# kit.net
KiCad netlist of a schematic drawn in EAGLE
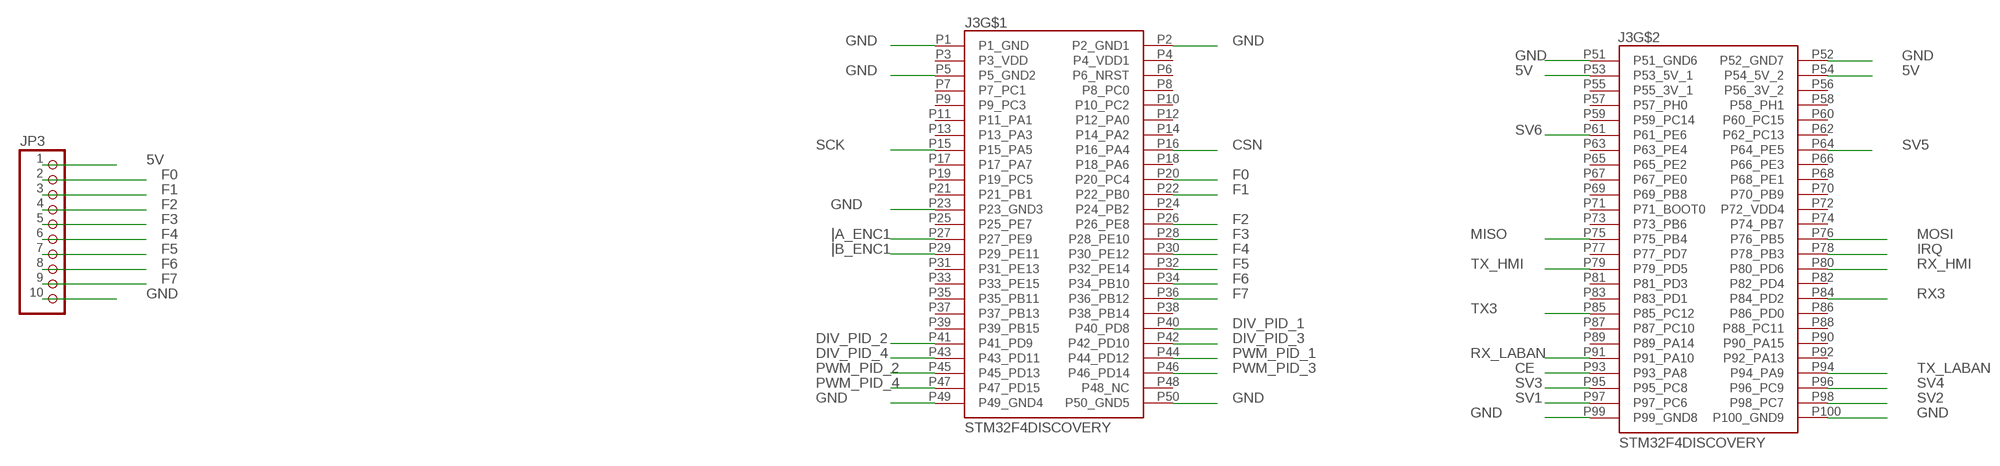
[diagram p0: schematic, sheet 1]
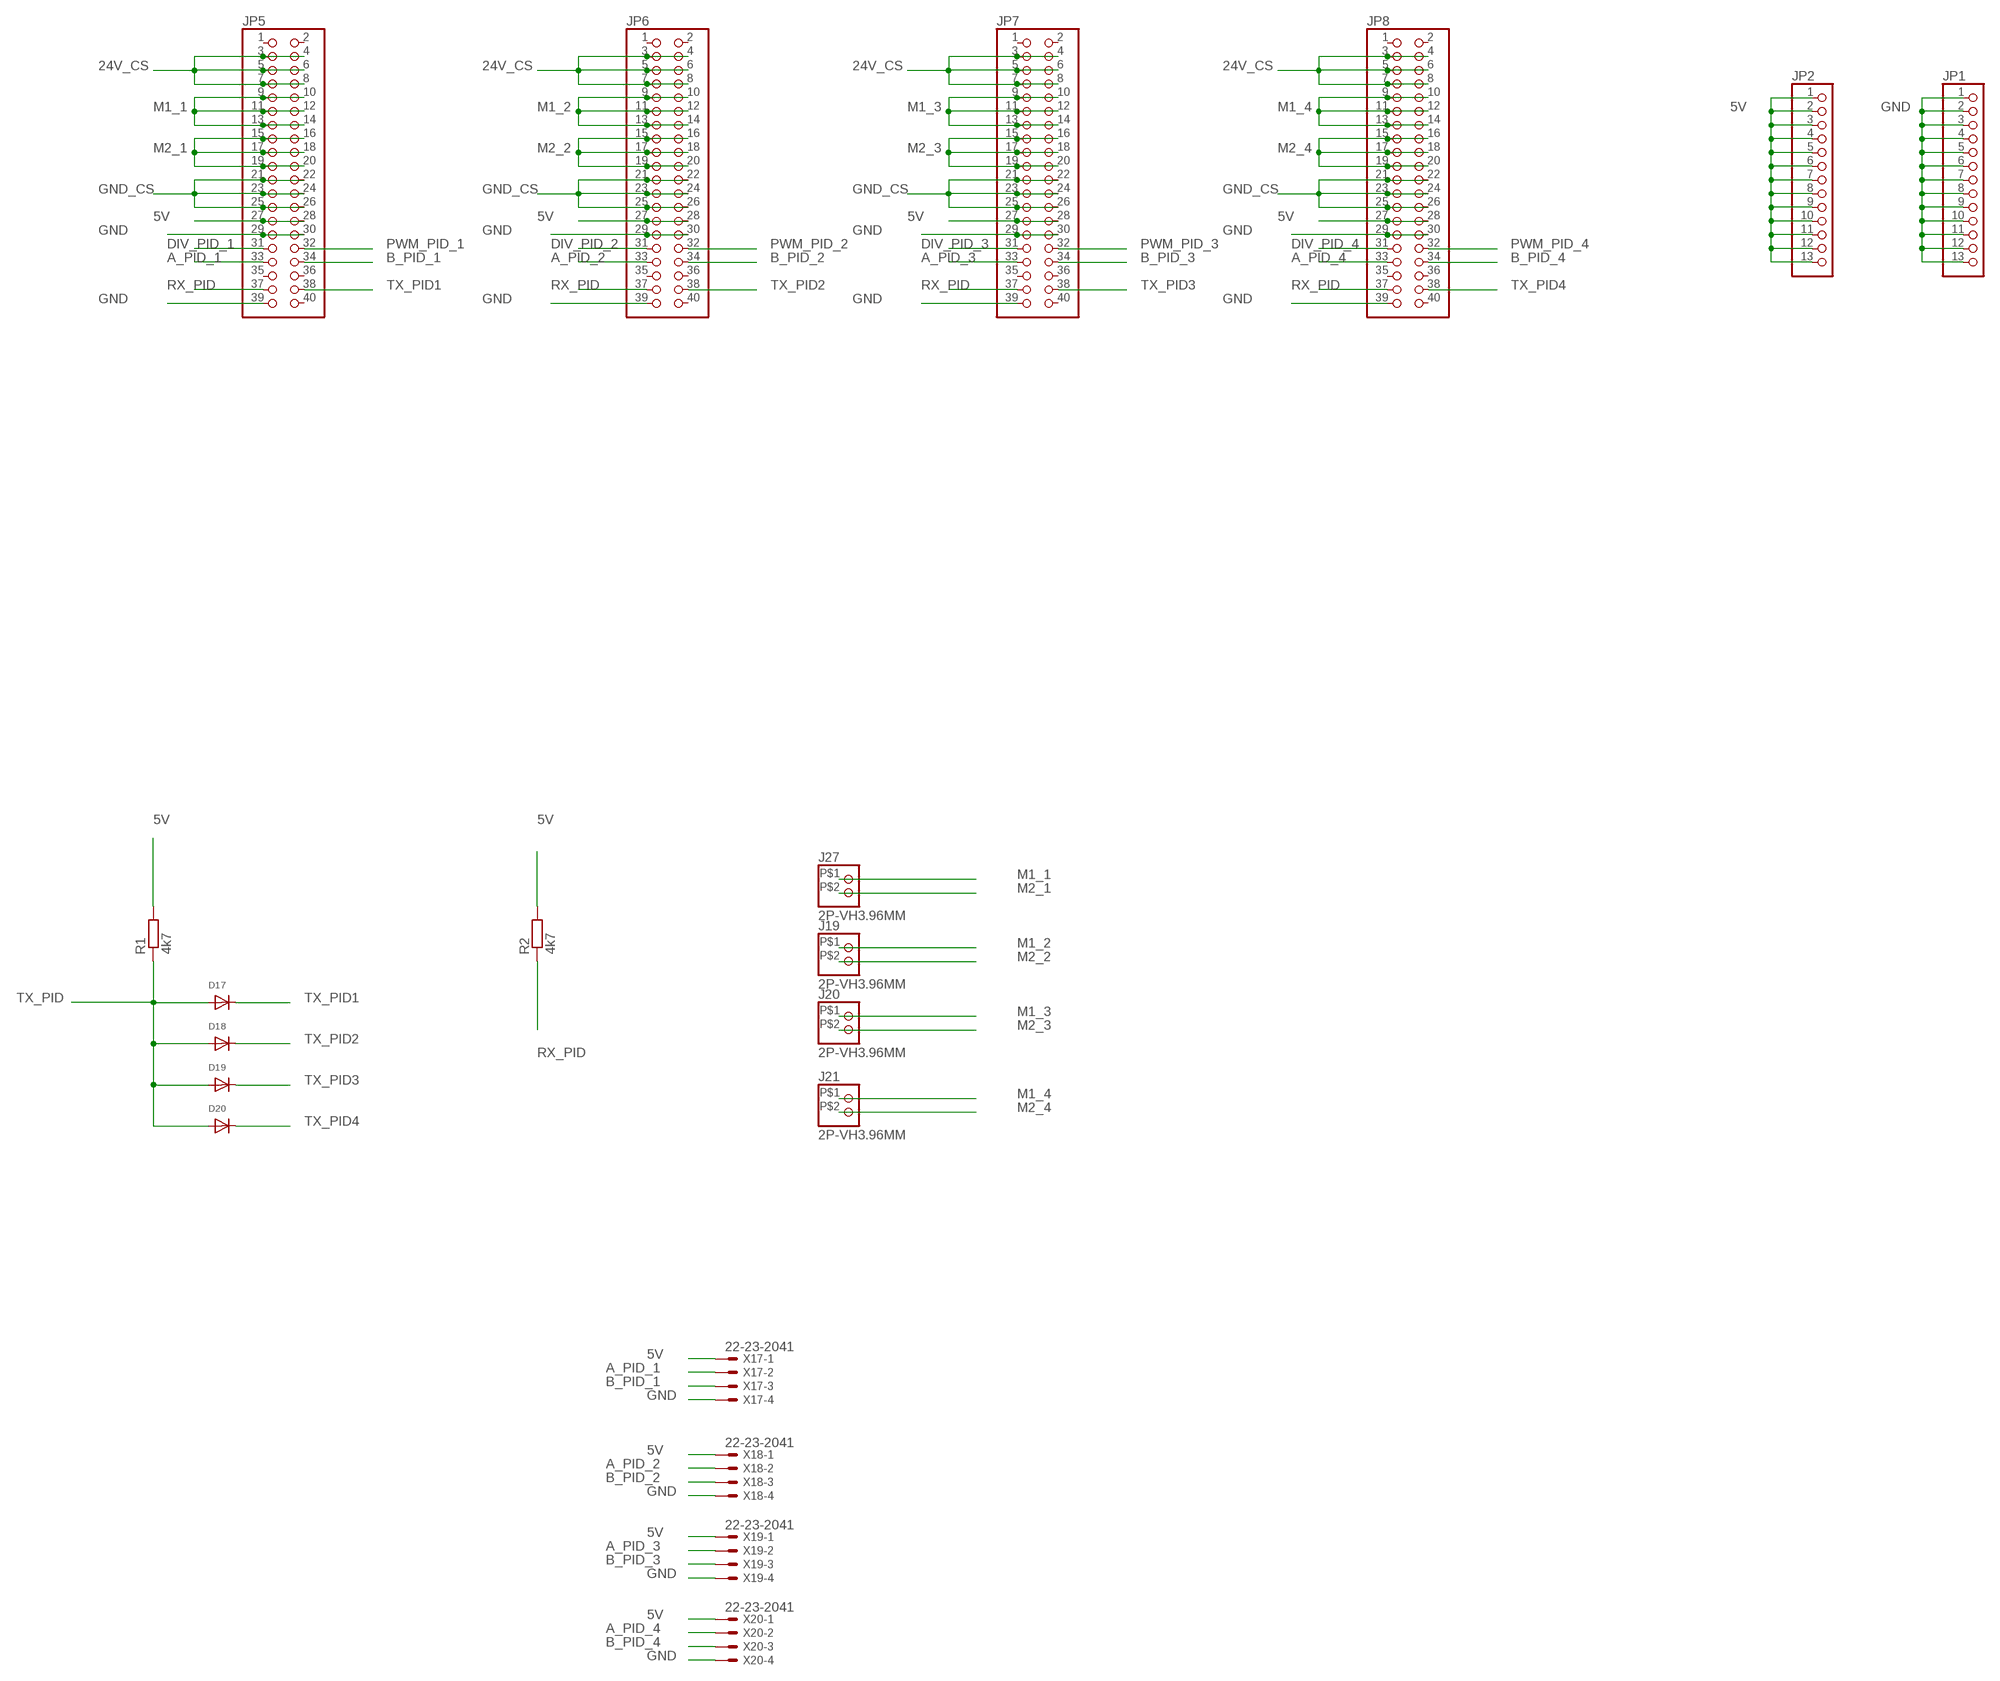
[diagram p1: schematic, sheet 2]
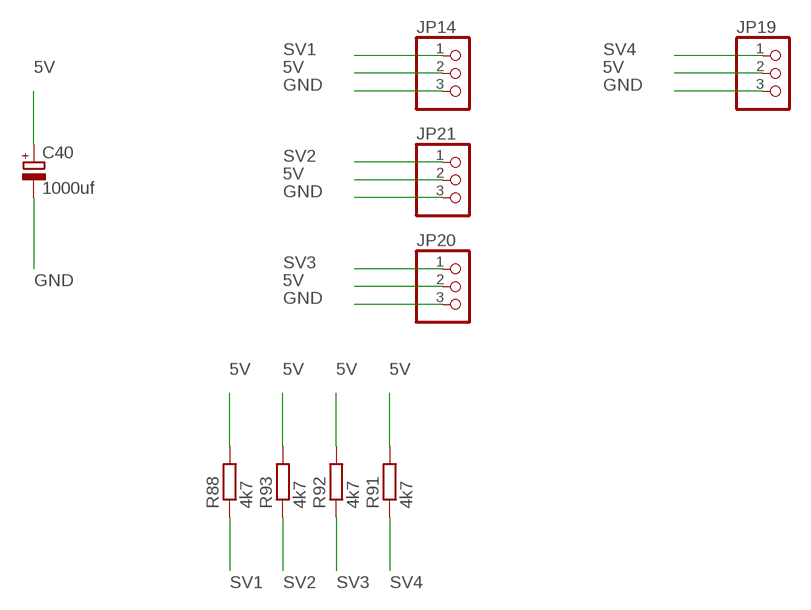
[diagram p2: schematic, sheet 3]
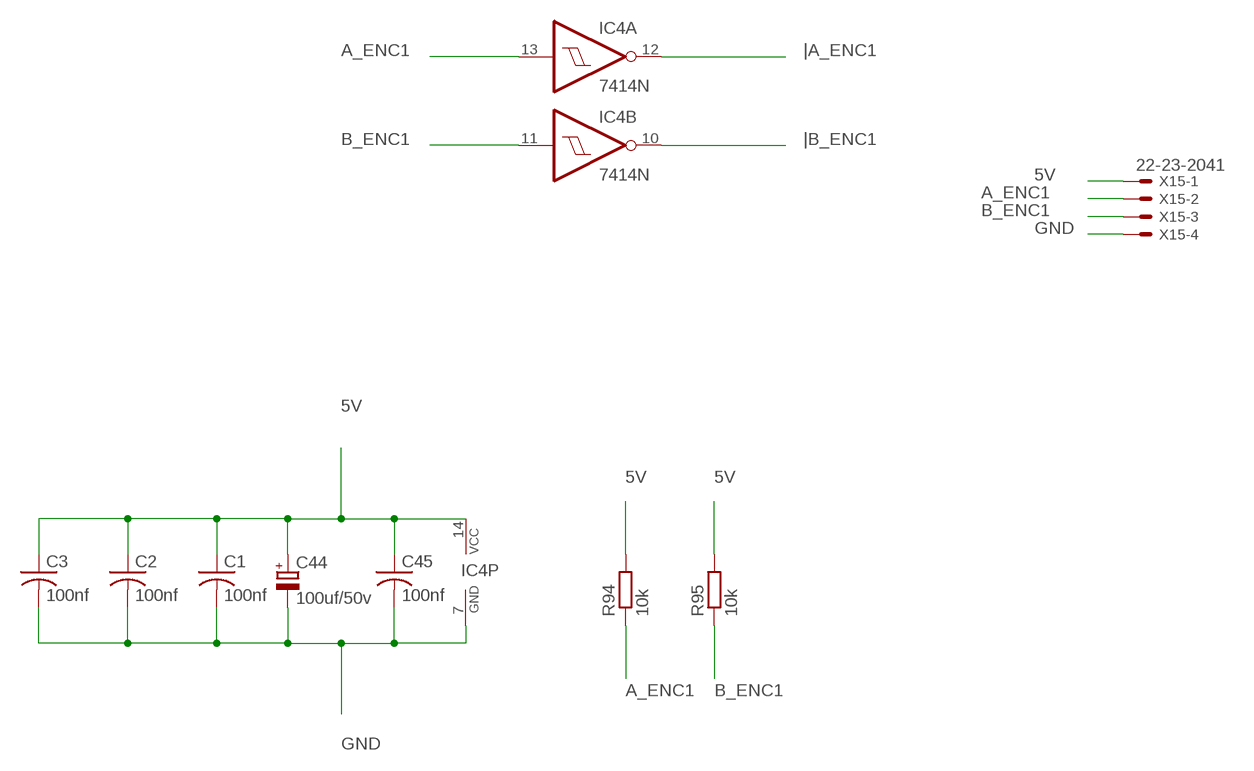
[diagram p3: schematic, sheet 4]
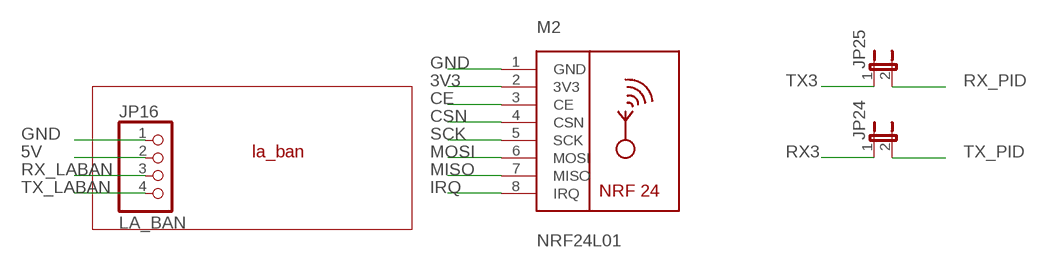
[diagram p4: schematic, sheet 5]
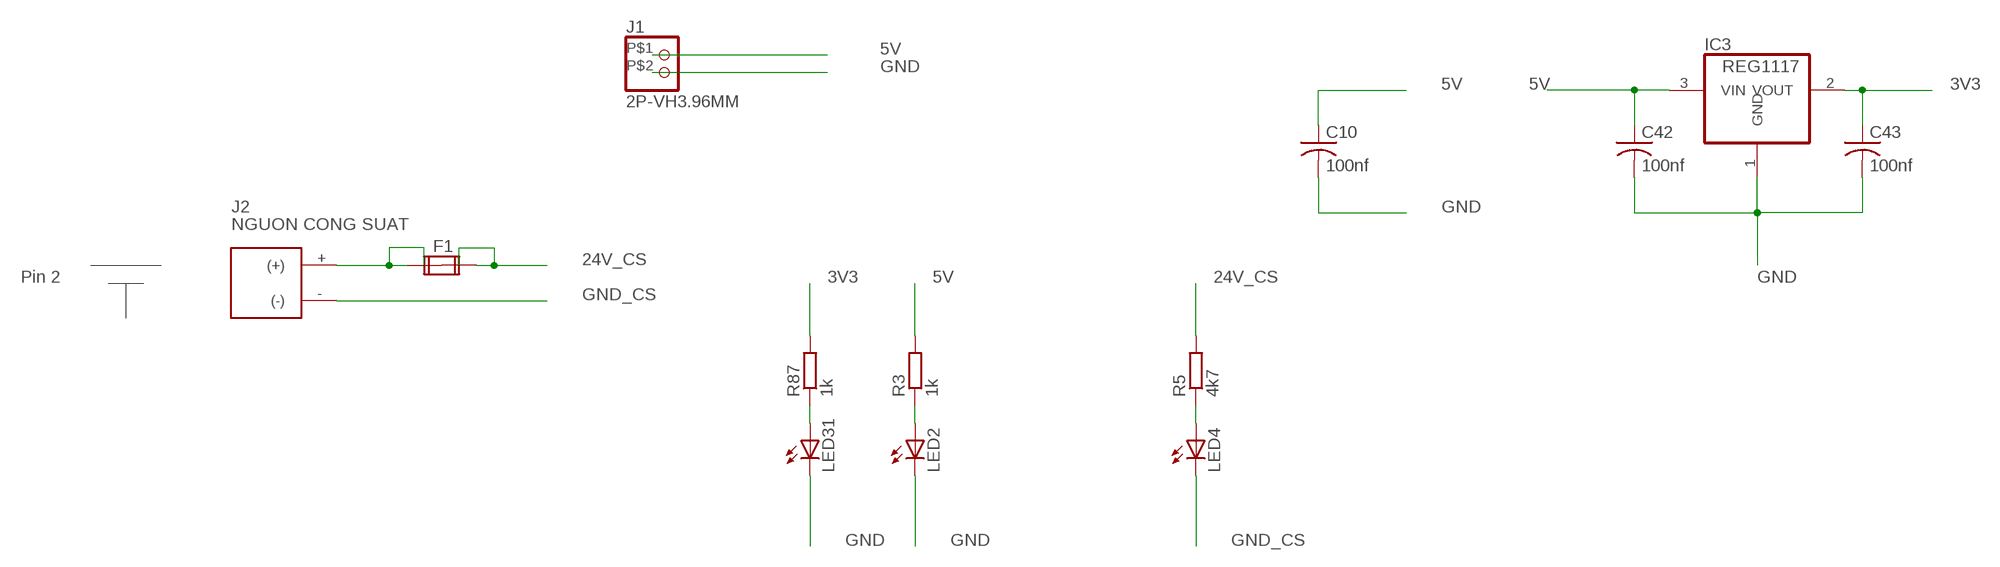
[diagram p5: schematic, sheet 6]

(export (version "E")
  (design (tool "Eeschema 10.0.6"))
  (components
    (comp (ref "C1")
      (value "100nf")
      (footprint "eagle-import:C050-025X075")
      (libsource (lib "eagle-import") (part "C-US050-025X075"))
    )
    (comp (ref "C2")
      (value "100nf")
      (footprint "eagle-import:C050-025X075")
      (libsource (lib "eagle-import") (part "C-US050-025X075"))
    )
    (comp (ref "C3")
      (value "100nf")
      (footprint "eagle-import:C050-025X075")
      (libsource (lib "eagle-import") (part "C-US050-025X075"))
    )
    (comp (ref "C44")
      (value "100uf/50v")
      (footprint "eagle-import:E5-10,5")
      (libsource (lib "eagle-import") (part "CPOL-EUE5-10.5"))
    )
    (comp (ref "C45")
      (value "100nf")
      (footprint "eagle-import:C050-025X075")
      (libsource (lib "eagle-import") (part "C-US050-025X075"))
    )
    (comp (ref "IC4")
      (value "7414N")
      (footprint "eagle-import:DIL14")
      (libsource (lib "eagle-import") (part "7414N"))
    )
    (comp (ref "R94")
      (value "10k")
      (footprint "eagle-import:0207_10")
      (libsource (lib "eagle-import") (part "R-EU_0207/10"))
    )
    (comp (ref "R95")
      (value "10k")
      (footprint "eagle-import:0207_10")
      (libsource (lib "eagle-import") (part "R-EU_0207/10"))
    )
    (comp (ref "X15")
      (value "22-23-2041")
      (footprint "eagle-import:22-23-2041")
      (fields (field (name "MF") "MOLEX"))
      (libsource (lib "eagle-import") (part "22-23-2041"))
    )
    (comp (ref "C40")
      (value "1000uf")
      (footprint "eagle-import:E5-10,5")
      (libsource (lib "eagle-import") (part "CPOL-EUE5-10.5"))
    )
    (comp (ref "JP14")
      (value "PINHD-1X3")
      (footprint "eagle-import:1X03")
      (libsource (lib "eagle-import") (part "PINHD-1X3"))
    )
    (comp (ref "JP19")
      (value "PINHD-1X3")
      (footprint "eagle-import:1X03")
      (libsource (lib "eagle-import") (part "PINHD-1X3"))
    )
    (comp (ref "JP20")
      (value "PINHD-1X3")
      (footprint "eagle-import:1X03")
      (libsource (lib "eagle-import") (part "PINHD-1X3"))
    )
    (comp (ref "JP21")
      (value "PINHD-1X3")
      (footprint "eagle-import:1X03")
      (libsource (lib "eagle-import") (part "PINHD-1X3"))
    )
    (comp (ref "R88")
      (value "4k7")
      (footprint "eagle-import:0207_10")
      (libsource (lib "eagle-import") (part "R-EU_0207/10"))
    )
    (comp (ref "R91")
      (value "4k7")
      (footprint "eagle-import:0207_10")
      (libsource (lib "eagle-import") (part "R-EU_0207/10"))
    )
    (comp (ref "R92")
      (value "4k7")
      (footprint "eagle-import:0207_10")
      (libsource (lib "eagle-import") (part "R-EU_0207/10"))
    )
    (comp (ref "R93")
      (value "4k7")
      (footprint "eagle-import:0207_10")
      (libsource (lib "eagle-import") (part "R-EU_0207/10"))
    )
    (comp (ref "J3")
      (value "STM32F4DISCOVERY")
      (footprint "eagle-import:STMICROELECTRONICS_STM32F4DISCOVERY")
      (fields (field (name "MF") "STMicroelectronics"))
      (libsource (lib "eagle-import") (part "STM32F4DISCOVERY"))
    )
    (comp (ref "JP3")
      (value "PINHD-1X10/90")
      (footprint "eagle-import:1X10_90")
      (libsource (lib "eagle-import") (part "PINHD-1X10/90"))
    )
    (comp (ref "C10")
      (value "100nf")
      (footprint "eagle-import:C050-025X075")
      (libsource (lib "eagle-import") (part "C-US050-025X075"))
    )
    (comp (ref "C42")
      (value "100nf")
      (footprint "eagle-import:C050-025X075")
      (libsource (lib "eagle-import") (part "C-US050-025X075"))
    )
    (comp (ref "C43")
      (value "100nf")
      (footprint "eagle-import:C050-025X075")
      (libsource (lib "eagle-import") (part "C-US050-025X075"))
    )
    (comp (ref "F1")
      (value "FUSE2P")
      (footprint "eagle-import:FUSE1")
      (libsource (lib "eagle-import") (part "FUSE2P"))
    )
    (comp (ref "IC3")
      (value "REG1117")
      (footprint "eagle-import:SOT223")
      (libsource (lib "eagle-import") (part "REG1117"))
    )
    (comp (ref "J1")
      (value "2P-VH3.96MM")
      (footprint "eagle-import:2P-VH3.96MM")
      (libsource (lib "eagle-import") (part "2P-VH3.96MM"))
    )
    (comp (ref "J2")
      (value "NGUON CONG SUAT")
      (footprint "eagle-import:XT-60")
      (libsource (lib "eagle-import") (part "JACK-DC"))
    )
    (comp (ref "LED2")
      (value "LED3MM")
      (footprint "eagle-import:LED3MM")
      (libsource (lib "eagle-import") (part "LED3MM"))
    )
    (comp (ref "LED4")
      (value "LED3MM")
      (footprint "eagle-import:LED3MM")
      (libsource (lib "eagle-import") (part "LED3MM"))
    )
    (comp (ref "LED31")
      (value "LED3MM")
      (footprint "eagle-import:LED3MM")
      (libsource (lib "eagle-import") (part "LED3MM"))
    )
    (comp (ref "R3")
      (value "1k")
      (footprint "eagle-import:0207_10")
      (libsource (lib "eagle-import") (part "R-EU_0207/10"))
    )
    (comp (ref "R5")
      (value "4k7")
      (footprint "eagle-import:0207_10")
      (libsource (lib "eagle-import") (part "R-EU_0207/10"))
    )
    (comp (ref "R87")
      (value "1k")
      (footprint "eagle-import:0207_10")
      (libsource (lib "eagle-import") (part "R-EU_0207/10"))
    )
    (comp (ref "D17")
      (value "DIODEDO-1N4148")
      (footprint "eagle-import:DO-1N4148")
      (libsource (lib "eagle-import") (part "DIODEDO-1N4148"))
    )
    (comp (ref "D18")
      (value "DIODEDO-1N4148")
      (footprint "eagle-import:DO-1N4148")
      (libsource (lib "eagle-import") (part "DIODEDO-1N4148"))
    )
    (comp (ref "D19")
      (value "DIODEDO-1N4148")
      (footprint "eagle-import:DO-1N4148")
      (libsource (lib "eagle-import") (part "DIODEDO-1N4148"))
    )
    (comp (ref "D20")
      (value "DIODEDO-1N4148")
      (footprint "eagle-import:DO-1N4148")
      (libsource (lib "eagle-import") (part "DIODEDO-1N4148"))
    )
    (comp (ref "J19")
      (value "2P-VH3.96MM")
      (footprint "eagle-import:2P-VH3.96MM")
      (libsource (lib "eagle-import") (part "2P-VH3.96MM"))
    )
    (comp (ref "J20")
      (value "2P-VH3.96MM")
      (footprint "eagle-import:2P-VH3.96MM")
      (libsource (lib "eagle-import") (part "2P-VH3.96MM"))
    )
    (comp (ref "J21")
      (value "2P-VH3.96MM")
      (footprint "eagle-import:2P-VH3.96MM")
      (libsource (lib "eagle-import") (part "2P-VH3.96MM"))
    )
    (comp (ref "J27")
      (value "2P-VH3.96MM")
      (footprint "eagle-import:2P-VH3.96MM")
      (libsource (lib "eagle-import") (part "2P-VH3.96MM"))
    )
    (comp (ref "JP1")
      (value "PINHD-1X13")
      (footprint "eagle-import:1X13")
      (libsource (lib "eagle-import") (part "PINHD-1X13"))
    )
    (comp (ref "JP2")
      (value "PINHD-1X13")
      (footprint "eagle-import:1X13")
      (libsource (lib "eagle-import") (part "PINHD-1X13"))
    )
    (comp (ref "JP5")
      (value "PINHD-2X20")
      (footprint "eagle-import:2X20")
      (libsource (lib "eagle-import") (part "PINHD-2X20"))
    )
    (comp (ref "JP6")
      (value "PINHD-2X20")
      (footprint "eagle-import:2X20")
      (libsource (lib "eagle-import") (part "PINHD-2X20"))
    )
    (comp (ref "JP7")
      (value "PINHD-2X20")
      (footprint "eagle-import:2X20")
      (libsource (lib "eagle-import") (part "PINHD-2X20"))
    )
    (comp (ref "JP8")
      (value "PINHD-2X20")
      (footprint "eagle-import:2X20")
      (libsource (lib "eagle-import") (part "PINHD-2X20"))
    )
    (comp (ref "R1")
      (value "4k7")
      (footprint "eagle-import:0207_10")
      (libsource (lib "eagle-import") (part "R-EU_0207/10"))
    )
    (comp (ref "R2")
      (value "4k7")
      (footprint "eagle-import:0207_10")
      (libsource (lib "eagle-import") (part "R-EU_0207/10"))
    )
    (comp (ref "X17")
      (value "22-23-2041")
      (footprint "eagle-import:22-23-2041")
      (fields (field (name "MF") "MOLEX"))
      (libsource (lib "eagle-import") (part "22-23-2041"))
    )
    (comp (ref "X18")
      (value "22-23-2041")
      (footprint "eagle-import:22-23-2041")
      (fields (field (name "MF") "MOLEX"))
      (libsource (lib "eagle-import") (part "22-23-2041"))
    )
    (comp (ref "X19")
      (value "22-23-2041")
      (footprint "eagle-import:22-23-2041")
      (fields (field (name "MF") "MOLEX"))
      (libsource (lib "eagle-import") (part "22-23-2041"))
    )
    (comp (ref "X20")
      (value "22-23-2041")
      (footprint "eagle-import:22-23-2041")
      (fields (field (name "MF") "MOLEX"))
      (libsource (lib "eagle-import") (part "22-23-2041"))
    )
    (comp (ref "JP16")
      (value "LA_BAN")
      (footprint "eagle-import:1X04")
      (libsource (lib "eagle-import") (part "PINHD-1X4"))
    )
    (comp (ref "JP24")
      (value "JP1E")
      (footprint "eagle-import:JP1")
      (libsource (lib "eagle-import") (part "JP1E"))
    )
    (comp (ref "JP25")
      (value "JP1E")
      (footprint "eagle-import:JP1")
      (libsource (lib "eagle-import") (part "JP1E"))
    )
    (comp (ref "M2")
      (value "NRF24L01")
      (footprint "eagle-import:NRF24L01_CHANCAM_ANTEN_ONBOARD")
      (libsource (lib "eagle-import") (part "NRF24L01"))
    )
  )
  (nets
    (net (code "1") (name "3V3") (class "Default")
      (node (ref "C43") (pin "1") (pinfunction "1_1") (pintype "passive"))
      (node (ref "IC3") (pin "2") (pinfunction "VOUT_2") (pintype "output"))
      (node (ref "M2") (pin "2") (pinfunction "3V3_2") (pintype "bidirectional"))
      (node (ref "R87") (pin "2") (pinfunction "2_2") (pintype "passive"))
    )
    (net (code "2") (name "5V") (class "Default")
      (node (ref "C1") (pin "1") (pinfunction "1_1") (pintype "passive"))
      (node (ref "C10") (pin "1") (pinfunction "1_1") (pintype "passive"))
      (node (ref "C2") (pin "1") (pinfunction "1_1") (pintype "passive"))
      (node (ref "C3") (pin "1") (pinfunction "1_1") (pintype "passive"))
      (node (ref "C40") (pin "+") (pinfunction "+_+") (pintype "passive"))
      (node (ref "C42") (pin "1") (pinfunction "1_1") (pintype "passive"))
      (node (ref "C44") (pin "+") (pinfunction "+_+") (pintype "passive"))
      (node (ref "C45") (pin "1") (pinfunction "1_1") (pintype "passive"))
      (node (ref "IC3") (pin "3") (pinfunction "VIN_3") (pintype "input"))
      (node (ref "IC4") (pin "14") (pinfunction "VCC_14") (pintype "power_in"))
      (node (ref "J1") (pin "P$1") (pinfunction "1_P$1") (pintype "passive"))
      (node (ref "J3") (pin "P53") (pinfunction "P53_5V_1_P53") (pintype "passive"))
      (node (ref "J3") (pin "P54") (pinfunction "P54_5V_2_P54") (pintype "passive"))
      (node (ref "JP14") (pin "2") (pinfunction "2_2") (pintype "passive"))
      (node (ref "JP16") (pin "2") (pinfunction "2_2") (pintype "passive"))
      (node (ref "JP19") (pin "2") (pinfunction "2_2") (pintype "passive"))
      (node (ref "JP2") (pin "1") (pinfunction "1_1") (pintype "passive"))
      (node (ref "JP2") (pin "10") (pinfunction "10_10") (pintype "passive"))
      (node (ref "JP2") (pin "11") (pinfunction "11_11") (pintype "passive"))
      (node (ref "JP2") (pin "12") (pinfunction "12_12") (pintype "passive"))
      (node (ref "JP2") (pin "13") (pinfunction "13_13") (pintype "passive"))
      (node (ref "JP2") (pin "2") (pinfunction "2_2") (pintype "passive"))
      (node (ref "JP2") (pin "3") (pinfunction "3_3") (pintype "passive"))
      (node (ref "JP2") (pin "4") (pinfunction "4_4") (pintype "passive"))
      (node (ref "JP2") (pin "5") (pinfunction "5_5") (pintype "passive"))
      (node (ref "JP2") (pin "6") (pinfunction "6_6") (pintype "passive"))
      (node (ref "JP2") (pin "7") (pinfunction "7_7") (pintype "passive"))
      (node (ref "JP2") (pin "8") (pinfunction "8_8") (pintype "passive"))
      (node (ref "JP2") (pin "9") (pinfunction "9_9") (pintype "passive"))
      (node (ref "JP20") (pin "2") (pinfunction "2_2") (pintype "passive"))
      (node (ref "JP21") (pin "2") (pinfunction "2_2") (pintype "passive"))
      (node (ref "JP3") (pin "1") (pinfunction "1_1") (pintype "passive"))
      (node (ref "JP5") (pin "27") (pinfunction "27_27") (pintype "passive"))
      (node (ref "JP5") (pin "28") (pinfunction "28_28") (pintype "passive"))
      (node (ref "JP6") (pin "27") (pinfunction "27_27") (pintype "passive"))
      (node (ref "JP6") (pin "28") (pinfunction "28_28") (pintype "passive"))
      (node (ref "JP7") (pin "27") (pinfunction "27_27") (pintype "passive"))
      (node (ref "JP7") (pin "28") (pinfunction "28_28") (pintype "passive"))
      (node (ref "JP8") (pin "27") (pinfunction "27_27") (pintype "passive"))
      (node (ref "JP8") (pin "28") (pinfunction "28_28") (pintype "passive"))
      (node (ref "R1") (pin "2") (pinfunction "2_2") (pintype "passive"))
      (node (ref "R2") (pin "2") (pinfunction "2_2") (pintype "passive"))
      (node (ref "R3") (pin "2") (pinfunction "2_2") (pintype "passive"))
      (node (ref "R88") (pin "2") (pinfunction "2_2") (pintype "passive"))
      (node (ref "R91") (pin "2") (pinfunction "2_2") (pintype "passive"))
      (node (ref "R92") (pin "2") (pinfunction "2_2") (pintype "passive"))
      (node (ref "R93") (pin "2") (pinfunction "2_2") (pintype "passive"))
      (node (ref "R94") (pin "2") (pinfunction "2_2") (pintype "passive"))
      (node (ref "R95") (pin "2") (pinfunction "2_2") (pintype "passive"))
      (node (ref "X15") (pin "1") (pinfunction "S_1") (pintype "passive"))
      (node (ref "X17") (pin "1") (pinfunction "S_1") (pintype "passive"))
      (node (ref "X18") (pin "1") (pinfunction "S_1") (pintype "passive"))
      (node (ref "X19") (pin "1") (pinfunction "S_1") (pintype "passive"))
      (node (ref "X20") (pin "1") (pinfunction "S_1") (pintype "passive"))
    )
    (net (code "3") (name "24V_CS") (class "Default")
      (node (ref "F1") (pin "2A") (pinfunction "2A_2A") (pintype "passive"))
      (node (ref "F1") (pin "2B") (pinfunction "2B_2B") (pintype "passive"))
      (node (ref "JP5") (pin "3") (pinfunction "3_3") (pintype "passive"))
      (node (ref "JP5") (pin "4") (pinfunction "4_4") (pintype "passive"))
      (node (ref "JP5") (pin "5") (pinfunction "5_5") (pintype "passive"))
      (node (ref "JP5") (pin "6") (pinfunction "6_6") (pintype "passive"))
      (node (ref "JP5") (pin "7") (pinfunction "7_7") (pintype "passive"))
      (node (ref "JP5") (pin "8") (pinfunction "8_8") (pintype "passive"))
      (node (ref "JP6") (pin "3") (pinfunction "3_3") (pintype "passive"))
      (node (ref "JP6") (pin "4") (pinfunction "4_4") (pintype "passive"))
      (node (ref "JP6") (pin "5") (pinfunction "5_5") (pintype "passive"))
      (node (ref "JP6") (pin "6") (pinfunction "6_6") (pintype "passive"))
      (node (ref "JP6") (pin "7") (pinfunction "7_7") (pintype "passive"))
      (node (ref "JP6") (pin "8") (pinfunction "8_8") (pintype "passive"))
      (node (ref "JP7") (pin "3") (pinfunction "3_3") (pintype "passive"))
      (node (ref "JP7") (pin "4") (pinfunction "4_4") (pintype "passive"))
      (node (ref "JP7") (pin "5") (pinfunction "5_5") (pintype "passive"))
      (node (ref "JP7") (pin "6") (pinfunction "6_6") (pintype "passive"))
      (node (ref "JP7") (pin "7") (pinfunction "7_7") (pintype "passive"))
      (node (ref "JP7") (pin "8") (pinfunction "8_8") (pintype "passive"))
      (node (ref "JP8") (pin "3") (pinfunction "3_3") (pintype "passive"))
      (node (ref "JP8") (pin "4") (pinfunction "4_4") (pintype "passive"))
      (node (ref "JP8") (pin "5") (pinfunction "5_5") (pintype "passive"))
      (node (ref "JP8") (pin "6") (pinfunction "6_6") (pintype "passive"))
      (node (ref "JP8") (pin "7") (pinfunction "7_7") (pintype "passive"))
      (node (ref "JP8") (pin "8") (pinfunction "8_8") (pintype "passive"))
      (node (ref "R5") (pin "2") (pinfunction "2_2") (pintype "passive"))
    )
    (net (code "4") (name "A_ENC1") (class "Default")
      (node (ref "IC4") (pin "13") (pinfunction "I_13") (pintype "input"))
      (node (ref "R94") (pin "1") (pinfunction "1_1") (pintype "passive"))
      (node (ref "X15") (pin "2") (pinfunction "S_2") (pintype "passive"))
    )
    (net (code "5") (name "A_PID_1") (class "Default")
      (node (ref "JP5") (pin "33") (pinfunction "33_33") (pintype "passive"))
      (node (ref "X17") (pin "2") (pinfunction "S_2") (pintype "passive"))
    )
    (net (code "6") (name "A_PID_2") (class "Default")
      (node (ref "JP6") (pin "33") (pinfunction "33_33") (pintype "passive"))
      (node (ref "X18") (pin "2") (pinfunction "S_2") (pintype "passive"))
    )
    (net (code "7") (name "A_PID_3") (class "Default")
      (node (ref "JP7") (pin "33") (pinfunction "33_33") (pintype "passive"))
      (node (ref "X19") (pin "2") (pinfunction "S_2") (pintype "passive"))
    )
    (net (code "8") (name "A_PID_4") (class "Default")
      (node (ref "JP8") (pin "33") (pinfunction "33_33") (pintype "passive"))
      (node (ref "X20") (pin "2") (pinfunction "S_2") (pintype "passive"))
    )
    (net (code "9") (name "B_ENC1") (class "Default")
      (node (ref "IC4") (pin "11") (pinfunction "I_11") (pintype "input"))
      (node (ref "R95") (pin "1") (pinfunction "1_1") (pintype "passive"))
      (node (ref "X15") (pin "3") (pinfunction "S_3") (pintype "passive"))
    )
    (net (code "10") (name "B_PID_1") (class "Default")
      (node (ref "JP5") (pin "34") (pinfunction "34_34") (pintype "passive"))
      (node (ref "X17") (pin "3") (pinfunction "S_3") (pintype "passive"))
    )
    (net (code "11") (name "B_PID_2") (class "Default")
      (node (ref "JP6") (pin "34") (pinfunction "34_34") (pintype "passive"))
      (node (ref "X18") (pin "3") (pinfunction "S_3") (pintype "passive"))
    )
    (net (code "12") (name "B_PID_3") (class "Default")
      (node (ref "JP7") (pin "34") (pinfunction "34_34") (pintype "passive"))
      (node (ref "X19") (pin "3") (pinfunction "S_3") (pintype "passive"))
    )
    (net (code "13") (name "B_PID_4") (class "Default")
      (node (ref "JP8") (pin "34") (pinfunction "34_34") (pintype "passive"))
      (node (ref "X20") (pin "3") (pinfunction "S_3") (pintype "passive"))
    )
    (net (code "14") (name "CE") (class "Default")
      (node (ref "J3") (pin "P93") (pinfunction "P93_PA8_P93") (pintype "passive"))
      (node (ref "M2") (pin "3") (pinfunction "CE_3") (pintype "bidirectional"))
    )
    (net (code "15") (name "CSN") (class "Default")
      (node (ref "J3") (pin "P16") (pinfunction "P16_PA4_P16") (pintype "passive"))
      (node (ref "M2") (pin "4") (pinfunction "CSN_4") (pintype "bidirectional"))
    )
    (net (code "16") (name "DIV_PID_1") (class "Default")
      (node (ref "J3") (pin "P40") (pinfunction "P40_PD8_P40") (pintype "passive"))
      (node (ref "JP5") (pin "31") (pinfunction "31_31") (pintype "passive"))
    )
    (net (code "17") (name "DIV_PID_2") (class "Default")
      (node (ref "J3") (pin "P41") (pinfunction "P41_PD9_P41") (pintype "passive"))
      (node (ref "JP6") (pin "31") (pinfunction "31_31") (pintype "passive"))
    )
    (net (code "18") (name "DIV_PID_3") (class "Default")
      (node (ref "J3") (pin "P42") (pinfunction "P42_PD10_P42") (pintype "passive"))
      (node (ref "JP7") (pin "31") (pinfunction "31_31") (pintype "passive"))
    )
    (net (code "19") (name "DIV_PID_4") (class "Default")
      (node (ref "J3") (pin "P43") (pinfunction "P43_PD11_P43") (pintype "passive"))
      (node (ref "JP8") (pin "31") (pinfunction "31_31") (pintype "passive"))
    )
    (net (code "20") (name "F0") (class "Default")
      (node (ref "J3") (pin "P20") (pinfunction "P20_PC4_P20") (pintype "passive"))
      (node (ref "JP3") (pin "2") (pinfunction "2_2") (pintype "passive"))
    )
    (net (code "21") (name "F1") (class "Default")
      (node (ref "J3") (pin "P22") (pinfunction "P22_PB0_P22") (pintype "passive"))
      (node (ref "JP3") (pin "3") (pinfunction "3_3") (pintype "passive"))
    )
    (net (code "22") (name "F2") (class "Default")
      (node (ref "J3") (pin "P26") (pinfunction "P26_PE8_P26") (pintype "passive"))
      (node (ref "JP3") (pin "4") (pinfunction "4_4") (pintype "passive"))
    )
    (net (code "23") (name "F3") (class "Default")
      (node (ref "J3") (pin "P28") (pinfunction "P28_PE10_P28") (pintype "passive"))
      (node (ref "JP3") (pin "5") (pinfunction "5_5") (pintype "passive"))
    )
    (net (code "24") (name "F4") (class "Default")
      (node (ref "J3") (pin "P30") (pinfunction "P30_PE12_P30") (pintype "passive"))
      (node (ref "JP3") (pin "6") (pinfunction "6_6") (pintype "passive"))
    )
    (net (code "25") (name "F5") (class "Default")
      (node (ref "J3") (pin "P32") (pinfunction "P32_PE14_P32") (pintype "passive"))
      (node (ref "JP3") (pin "7") (pinfunction "7_7") (pintype "passive"))
    )
    (net (code "26") (name "F6") (class "Default")
      (node (ref "J3") (pin "P34") (pinfunction "P34_PB10_P34") (pintype "passive"))
      (node (ref "JP3") (pin "8") (pinfunction "8_8") (pintype "passive"))
    )
    (net (code "27") (name "F7") (class "Default")
      (node (ref "J3") (pin "P36") (pinfunction "P36_PB12_P36") (pintype "passive"))
      (node (ref "JP3") (pin "9") (pinfunction "9_9") (pintype "passive"))
    )
    (net (code "28") (name "GND") (class "Default")
      (node (ref "C1") (pin "2") (pinfunction "2_2") (pintype "passive"))
      (node (ref "C10") (pin "2") (pinfunction "2_2") (pintype "passive"))
      (node (ref "C2") (pin "2") (pinfunction "2_2") (pintype "passive"))
      (node (ref "C3") (pin "2") (pinfunction "2_2") (pintype "passive"))
      (node (ref "C40") (pin "-") (pinfunction "-_-") (pintype "passive"))
      (node (ref "C42") (pin "2") (pinfunction "2_2") (pintype "passive"))
      (node (ref "C43") (pin "2") (pinfunction "2_2") (pintype "passive"))
      (node (ref "C44") (pin "-") (pinfunction "-_-") (pintype "passive"))
      (node (ref "C45") (pin "2") (pinfunction "2_2") (pintype "passive"))
      (node (ref "IC3") (pin "1") (pinfunction "GND_1") (pintype "power_in"))
      (node (ref "IC4") (pin "7") (pinfunction "GND_7") (pintype "power_in"))
      (node (ref "J1") (pin "P$2") (pinfunction "2_P$2") (pintype "passive"))
      (node (ref "J3") (pin "P1") (pinfunction "P1_GND_P1") (pintype "passive"))
      (node (ref "J3") (pin "P100") (pinfunction "P100_GND9_P100") (pintype "passive"))
      (node (ref "J3") (pin "P2") (pinfunction "P2_GND1_P2") (pintype "passive"))
      (node (ref "J3") (pin "P23") (pinfunction "P23_GND3_P23") (pintype "passive"))
      (node (ref "J3") (pin "P49") (pinfunction "P49_GND4_P49") (pintype "passive"))
      (node (ref "J3") (pin "P5") (pinfunction "P5_GND2_P5") (pintype "passive"))
      (node (ref "J3") (pin "P50") (pinfunction "P50_GND5_P50") (pintype "passive"))
      (node (ref "J3") (pin "P51") (pinfunction "P51_GND6_P51") (pintype "passive"))
      (node (ref "J3") (pin "P52") (pinfunction "P52_GND7_P52") (pintype "passive"))
      (node (ref "J3") (pin "P99") (pinfunction "P99_GND8_P99") (pintype "passive"))
      (node (ref "JP1") (pin "1") (pinfunction "1_1") (pintype "passive"))
      (node (ref "JP1") (pin "10") (pinfunction "10_10") (pintype "passive"))
      (node (ref "JP1") (pin "11") (pinfunction "11_11") (pintype "passive"))
      (node (ref "JP1") (pin "12") (pinfunction "12_12") (pintype "passive"))
      (node (ref "JP1") (pin "13") (pinfunction "13_13") (pintype "passive"))
      (node (ref "JP1") (pin "2") (pinfunction "2_2") (pintype "passive"))
      (node (ref "JP1") (pin "3") (pinfunction "3_3") (pintype "passive"))
      (node (ref "JP1") (pin "4") (pinfunction "4_4") (pintype "passive"))
      (node (ref "JP1") (pin "5") (pinfunction "5_5") (pintype "passive"))
      (node (ref "JP1") (pin "6") (pinfunction "6_6") (pintype "passive"))
      (node (ref "JP1") (pin "7") (pinfunction "7_7") (pintype "passive"))
      (node (ref "JP1") (pin "8") (pinfunction "8_8") (pintype "passive"))
      (node (ref "JP1") (pin "9") (pinfunction "9_9") (pintype "passive"))
      (node (ref "JP14") (pin "3") (pinfunction "3_3") (pintype "passive"))
      (node (ref "JP16") (pin "1") (pinfunction "1_1") (pintype "passive"))
      (node (ref "JP19") (pin "3") (pinfunction "3_3") (pintype "passive"))
      (node (ref "JP20") (pin "3") (pinfunction "3_3") (pintype "passive"))
      (node (ref "JP21") (pin "3") (pinfunction "3_3") (pintype "passive"))
      (node (ref "JP3") (pin "10") (pinfunction "10_10") (pintype "passive"))
      (node (ref "JP5") (pin "29") (pinfunction "29_29") (pintype "passive"))
      (node (ref "JP5") (pin "30") (pinfunction "30_30") (pintype "passive"))
      (node (ref "JP5") (pin "39") (pinfunction "39_39") (pintype "passive"))
      (node (ref "JP6") (pin "29") (pinfunction "29_29") (pintype "passive"))
      (node (ref "JP6") (pin "30") (pinfunction "30_30") (pintype "passive"))
      (node (ref "JP6") (pin "39") (pinfunction "39_39") (pintype "passive"))
      (node (ref "JP7") (pin "29") (pinfunction "29_29") (pintype "passive"))
      (node (ref "JP7") (pin "30") (pinfunction "30_30") (pintype "passive"))
      (node (ref "JP7") (pin "39") (pinfunction "39_39") (pintype "passive"))
      (node (ref "JP8") (pin "29") (pinfunction "29_29") (pintype "passive"))
      (node (ref "JP8") (pin "30") (pinfunction "30_30") (pintype "passive"))
      (node (ref "JP8") (pin "39") (pinfunction "39_39") (pintype "passive"))
      (node (ref "LED2") (pin "K") (pinfunction "C_K") (pintype "passive"))
      (node (ref "LED31") (pin "K") (pinfunction "C_K") (pintype "passive"))
      (node (ref "M2") (pin "1") (pinfunction "GND_1") (pintype "bidirectional"))
      (node (ref "X15") (pin "4") (pinfunction "S_4") (pintype "passive"))
      (node (ref "X17") (pin "4") (pinfunction "S_4") (pintype "passive"))
      (node (ref "X18") (pin "4") (pinfunction "S_4") (pintype "passive"))
      (node (ref "X19") (pin "4") (pinfunction "S_4") (pintype "passive"))
      (node (ref "X20") (pin "4") (pinfunction "S_4") (pintype "passive"))
    )
    (net (code "29") (name "GND_CS") (class "Default")
      (node (ref "J2") (pin "-") (pinfunction "(-)_-") (pintype "bidirectional"))
      (node (ref "JP5") (pin "21") (pinfunction "21_21") (pintype "passive"))
      (node (ref "JP5") (pin "22") (pinfunction "22_22") (pintype "passive"))
      (node (ref "JP5") (pin "23") (pinfunction "23_23") (pintype "passive"))
      (node (ref "JP5") (pin "24") (pinfunction "24_24") (pintype "passive"))
      (node (ref "JP5") (pin "25") (pinfunction "25_25") (pintype "passive"))
      (node (ref "JP5") (pin "26") (pinfunction "26_26") (pintype "passive"))
      (node (ref "JP6") (pin "21") (pinfunction "21_21") (pintype "passive"))
      (node (ref "JP6") (pin "22") (pinfunction "22_22") (pintype "passive"))
      (node (ref "JP6") (pin "23") (pinfunction "23_23") (pintype "passive"))
      (node (ref "JP6") (pin "24") (pinfunction "24_24") (pintype "passive"))
      (node (ref "JP6") (pin "25") (pinfunction "25_25") (pintype "passive"))
      (node (ref "JP6") (pin "26") (pinfunction "26_26") (pintype "passive"))
      (node (ref "JP7") (pin "21") (pinfunction "21_21") (pintype "passive"))
      (node (ref "JP7") (pin "22") (pinfunction "22_22") (pintype "passive"))
      (node (ref "JP7") (pin "23") (pinfunction "23_23") (pintype "passive"))
      (node (ref "JP7") (pin "24") (pinfunction "24_24") (pintype "passive"))
      (node (ref "JP7") (pin "25") (pinfunction "25_25") (pintype "passive"))
      (node (ref "JP7") (pin "26") (pinfunction "26_26") (pintype "passive"))
      (node (ref "JP8") (pin "21") (pinfunction "21_21") (pintype "passive"))
      (node (ref "JP8") (pin "22") (pinfunction "22_22") (pintype "passive"))
      (node (ref "JP8") (pin "23") (pinfunction "23_23") (pintype "passive"))
      (node (ref "JP8") (pin "24") (pinfunction "24_24") (pintype "passive"))
      (node (ref "JP8") (pin "25") (pinfunction "25_25") (pintype "passive"))
      (node (ref "JP8") (pin "26") (pinfunction "26_26") (pintype "passive"))
      (node (ref "LED4") (pin "K") (pinfunction "C_K") (pintype "passive"))
    )
    (net (code "30") (name "IRQ") (class "Default")
      (node (ref "J3") (pin "P78") (pinfunction "P78_PB3_P78") (pintype "passive"))
      (node (ref "M2") (pin "8") (pinfunction "IRQ_8") (pintype "bidirectional"))
    )
    (net (code "31") (name "M1_1") (class "Default")
      (node (ref "J27") (pin "P$1") (pinfunction "1_P$1") (pintype "passive"))
      (node (ref "JP5") (pin "10") (pinfunction "10_10") (pintype "passive"))
      (node (ref "JP5") (pin "11") (pinfunction "11_11") (pintype "passive"))
      (node (ref "JP5") (pin "12") (pinfunction "12_12") (pintype "passive"))
      (node (ref "JP5") (pin "13") (pinfunction "13_13") (pintype "passive"))
      (node (ref "JP5") (pin "14") (pinfunction "14_14") (pintype "passive"))
      (node (ref "JP5") (pin "9") (pinfunction "9_9") (pintype "passive"))
    )
    (net (code "32") (name "M1_2") (class "Default")
      (node (ref "J19") (pin "P$1") (pinfunction "1_P$1") (pintype "passive"))
      (node (ref "JP6") (pin "10") (pinfunction "10_10") (pintype "passive"))
      (node (ref "JP6") (pin "11") (pinfunction "11_11") (pintype "passive"))
      (node (ref "JP6") (pin "12") (pinfunction "12_12") (pintype "passive"))
      (node (ref "JP6") (pin "13") (pinfunction "13_13") (pintype "passive"))
      (node (ref "JP6") (pin "14") (pinfunction "14_14") (pintype "passive"))
      (node (ref "JP6") (pin "9") (pinfunction "9_9") (pintype "passive"))
    )
    (net (code "33") (name "M1_3") (class "Default")
      (node (ref "J20") (pin "P$1") (pinfunction "1_P$1") (pintype "passive"))
      (node (ref "JP7") (pin "10") (pinfunction "10_10") (pintype "passive"))
      (node (ref "JP7") (pin "11") (pinfunction "11_11") (pintype "passive"))
      (node (ref "JP7") (pin "12") (pinfunction "12_12") (pintype "passive"))
      (node (ref "JP7") (pin "13") (pinfunction "13_13") (pintype "passive"))
      (node (ref "JP7") (pin "14") (pinfunction "14_14") (pintype "passive"))
      (node (ref "JP7") (pin "9") (pinfunction "9_9") (pintype "passive"))
    )
    (net (code "34") (name "M1_4") (class "Default")
      (node (ref "J21") (pin "P$1") (pinfunction "1_P$1") (pintype "passive"))
      (node (ref "JP8") (pin "10") (pinfunction "10_10") (pintype "passive"))
      (node (ref "JP8") (pin "11") (pinfunction "11_11") (pintype "passive"))
      (node (ref "JP8") (pin "12") (pinfunction "12_12") (pintype "passive"))
      (node (ref "JP8") (pin "13") (pinfunction "13_13") (pintype "passive"))
      (node (ref "JP8") (pin "14") (pinfunction "14_14") (pintype "passive"))
      (node (ref "JP8") (pin "9") (pinfunction "9_9") (pintype "passive"))
    )
    (net (code "35") (name "M2_1") (class "Default")
      (node (ref "J27") (pin "P$2") (pinfunction "2_P$2") (pintype "passive"))
      (node (ref "JP5") (pin "15") (pinfunction "15_15") (pintype "passive"))
      (node (ref "JP5") (pin "16") (pinfunction "16_16") (pintype "passive"))
      (node (ref "JP5") (pin "17") (pinfunction "17_17") (pintype "passive"))
      (node (ref "JP5") (pin "18") (pinfunction "18_18") (pintype "passive"))
      (node (ref "JP5") (pin "19") (pinfunction "19_19") (pintype "passive"))
      (node (ref "JP5") (pin "20") (pinfunction "20_20") (pintype "passive"))
    )
    (net (code "36") (name "M2_2") (class "Default")
      (node (ref "J19") (pin "P$2") (pinfunction "2_P$2") (pintype "passive"))
      (node (ref "JP6") (pin "15") (pinfunction "15_15") (pintype "passive"))
      (node (ref "JP6") (pin "16") (pinfunction "16_16") (pintype "passive"))
      (node (ref "JP6") (pin "17") (pinfunction "17_17") (pintype "passive"))
      (node (ref "JP6") (pin "18") (pinfunction "18_18") (pintype "passive"))
      (node (ref "JP6") (pin "19") (pinfunction "19_19") (pintype "passive"))
      (node (ref "JP6") (pin "20") (pinfunction "20_20") (pintype "passive"))
    )
    (net (code "37") (name "M2_3") (class "Default")
      (node (ref "J20") (pin "P$2") (pinfunction "2_P$2") (pintype "passive"))
      (node (ref "JP7") (pin "15") (pinfunction "15_15") (pintype "passive"))
      (node (ref "JP7") (pin "16") (pinfunction "16_16") (pintype "passive"))
      (node (ref "JP7") (pin "17") (pinfunction "17_17") (pintype "passive"))
      (node (ref "JP7") (pin "18") (pinfunction "18_18") (pintype "passive"))
      (node (ref "JP7") (pin "19") (pinfunction "19_19") (pintype "passive"))
      (node (ref "JP7") (pin "20") (pinfunction "20_20") (pintype "passive"))
    )
    (net (code "38") (name "M2_4") (class "Default")
      (node (ref "J21") (pin "P$2") (pinfunction "2_P$2") (pintype "passive"))
      (node (ref "JP8") (pin "15") (pinfunction "15_15") (pintype "passive"))
      (node (ref "JP8") (pin "16") (pinfunction "16_16") (pintype "passive"))
      (node (ref "JP8") (pin "17") (pinfunction "17_17") (pintype "passive"))
      (node (ref "JP8") (pin "18") (pinfunction "18_18") (pintype "passive"))
      (node (ref "JP8") (pin "19") (pinfunction "19_19") (pintype "passive"))
      (node (ref "JP8") (pin "20") (pinfunction "20_20") (pintype "passive"))
    )
    (net (code "39") (name "MISO") (class "Default")
      (node (ref "J3") (pin "P75") (pinfunction "P75_PB4_P75") (pintype "passive"))
      (node (ref "M2") (pin "7") (pinfunction "MISO_7") (pintype "bidirectional"))
    )
    (net (code "40") (name "MOSI") (class "Default")
      (node (ref "J3") (pin "P76") (pinfunction "P76_PB5_P76") (pintype "passive"))
      (node (ref "M2") (pin "6") (pinfunction "MOSI_6") (pintype "bidirectional"))
    )
    (net (code "41") (name "Net-(J2-(+))") (class "Default")
      (node (ref "F1") (pin "1A") (pinfunction "1A_1A") (pintype "passive"))
      (node (ref "F1") (pin "1B") (pinfunction "1B_1B") (pintype "passive"))
      (node (ref "J2") (pin "+") (pinfunction "(+)_+") (pintype "bidirectional"))
    )
    (net (code "42") (name "Net-(LED2-PadA)") (class "Default")
      (node (ref "LED2") (pin "A") (pinfunction "A_A") (pintype "passive"))
      (node (ref "R3") (pin "1") (pinfunction "1_1") (pintype "passive"))
    )
    (net (code "43") (name "Net-(LED4-PadA)") (class "Default")
      (node (ref "LED4") (pin "A") (pinfunction "A_A") (pintype "passive"))
      (node (ref "R5") (pin "1") (pinfunction "1_1") (pintype "passive"))
    )
    (net (code "44") (name "Net-(LED31-PadA)") (class "Default")
      (node (ref "LED31") (pin "A") (pinfunction "A_A") (pintype "passive"))
      (node (ref "R87") (pin "1") (pinfunction "1_1") (pintype "passive"))
    )
    (net (code "45") (name "PWM_PID_1") (class "Default")
      (node (ref "J3") (pin "P44") (pinfunction "P44_PD12_P44") (pintype "passive"))
      (node (ref "JP5") (pin "32") (pinfunction "32_32") (pintype "passive"))
    )
    (net (code "46") (name "PWM_PID_2") (class "Default")
      (node (ref "J3") (pin "P45") (pinfunction "P45_PD13_P45") (pintype "passive"))
      (node (ref "JP6") (pin "32") (pinfunction "32_32") (pintype "passive"))
    )
    (net (code "47") (name "PWM_PID_3") (class "Default")
      (node (ref "J3") (pin "P46") (pinfunction "P46_PD14_P46") (pintype "passive"))
      (node (ref "JP7") (pin "32") (pinfunction "32_32") (pintype "passive"))
    )
    (net (code "48") (name "PWM_PID_4") (class "Default")
      (node (ref "J3") (pin "P47") (pinfunction "P47_PD15_P47") (pintype "passive"))
      (node (ref "JP8") (pin "32") (pinfunction "32_32") (pintype "passive"))
    )
    (net (code "49") (name "RX3") (class "Default")
      (node (ref "J3") (pin "P84") (pinfunction "P84_PD2_P84") (pintype "passive"))
      (node (ref "JP24") (pin "1") (pinfunction "1_1") (pintype "passive"))
    )
    (net (code "50") (name "RX_HMI") (class "Default")
      (node (ref "J3") (pin "P80") (pinfunction "P80_PD6_P80") (pintype "passive"))
    )
    (net (code "51") (name "RX_LABAN") (class "Default")
      (node (ref "J3") (pin "P91") (pinfunction "P91_PA10_P91") (pintype "passive"))
      (node (ref "JP16") (pin "3") (pinfunction "3_3") (pintype "passive"))
    )
    (net (code "52") (name "RX_PID") (class "Default")
      (node (ref "JP25") (pin "2") (pinfunction "2_2") (pintype "passive"))
      (node (ref "JP5") (pin "37") (pinfunction "37_37") (pintype "passive"))
      (node (ref "JP6") (pin "37") (pinfunction "37_37") (pintype "passive"))
      (node (ref "JP7") (pin "37") (pinfunction "37_37") (pintype "passive"))
      (node (ref "JP8") (pin "37") (pinfunction "37_37") (pintype "passive"))
      (node (ref "R2") (pin "1") (pinfunction "1_1") (pintype "passive"))
    )
    (net (code "53") (name "SCK") (class "Default")
      (node (ref "J3") (pin "P15") (pinfunction "P15_PA5_P15") (pintype "passive"))
      (node (ref "M2") (pin "5") (pinfunction "SCK_5") (pintype "bidirectional"))
    )
    (net (code "54") (name "SV1") (class "Default")
      (node (ref "J3") (pin "P97") (pinfunction "P97_PC6_P97") (pintype "passive"))
      (node (ref "JP14") (pin "1") (pinfunction "1_1") (pintype "passive"))
      (node (ref "R88") (pin "1") (pinfunction "1_1") (pintype "passive"))
    )
    (net (code "55") (name "SV2") (class "Default")
      (node (ref "J3") (pin "P98") (pinfunction "P98_PC7_P98") (pintype "passive"))
      (node (ref "JP21") (pin "1") (pinfunction "1_1") (pintype "passive"))
      (node (ref "R93") (pin "1") (pinfunction "1_1") (pintype "passive"))
    )
    (net (code "56") (name "SV3") (class "Default")
      (node (ref "J3") (pin "P95") (pinfunction "P95_PC8_P95") (pintype "passive"))
      (node (ref "JP20") (pin "1") (pinfunction "1_1") (pintype "passive"))
      (node (ref "R92") (pin "1") (pinfunction "1_1") (pintype "passive"))
    )
    (net (code "57") (name "SV4") (class "Default")
      (node (ref "J3") (pin "P96") (pinfunction "P96_PC9_P96") (pintype "passive"))
      (node (ref "JP19") (pin "1") (pinfunction "1_1") (pintype "passive"))
      (node (ref "R91") (pin "1") (pinfunction "1_1") (pintype "passive"))
    )
    (net (code "58") (name "SV5") (class "Default")
      (node (ref "J3") (pin "P64") (pinfunction "P64_PE5_P64") (pintype "passive"))
    )
    (net (code "59") (name "SV6") (class "Default")
      (node (ref "J3") (pin "P61") (pinfunction "P61_PE6_P61") (pintype "passive"))
    )
    (net (code "60") (name "TX3") (class "Default")
      (node (ref "J3") (pin "P85") (pinfunction "P85_PC12_P85") (pintype "passive"))
      (node (ref "JP25") (pin "1") (pinfunction "1_1") (pintype "passive"))
    )
    (net (code "61") (name "TX_HMI") (class "Default")
      (node (ref "J3") (pin "P79") (pinfunction "P79_PD5_P79") (pintype "passive"))
    )
    (net (code "62") (name "TX_LABAN") (class "Default")
      (node (ref "J3") (pin "P94") (pinfunction "P94_PA9_P94") (pintype "passive"))
      (node (ref "JP16") (pin "4") (pinfunction "4_4") (pintype "passive"))
    )
    (net (code "63") (name "TX_PID") (class "Default")
      (node (ref "D17") (pin "A") (pinfunction "A_A") (pintype "passive"))
      (node (ref "D18") (pin "A") (pinfunction "A_A") (pintype "passive"))
      (node (ref "D19") (pin "A") (pinfunction "A_A") (pintype "passive"))
      (node (ref "D20") (pin "A") (pinfunction "A_A") (pintype "passive"))
      (node (ref "JP24") (pin "2") (pinfunction "2_2") (pintype "passive"))
      (node (ref "R1") (pin "1") (pinfunction "1_1") (pintype "passive"))
    )
    (net (code "64") (name "TX_PID1") (class "Default")
      (node (ref "D17") (pin "C") (pinfunction "C_C") (pintype "passive"))
      (node (ref "JP5") (pin "38") (pinfunction "38_38") (pintype "passive"))
    )
    (net (code "65") (name "TX_PID2") (class "Default")
      (node (ref "D18") (pin "C") (pinfunction "C_C") (pintype "passive"))
      (node (ref "JP6") (pin "38") (pinfunction "38_38") (pintype "passive"))
    )
    (net (code "66") (name "TX_PID3") (class "Default")
      (node (ref "D19") (pin "C") (pinfunction "C_C") (pintype "passive"))
      (node (ref "JP7") (pin "38") (pinfunction "38_38") (pintype "passive"))
    )
    (net (code "67") (name "TX_PID4") (class "Default")
      (node (ref "D20") (pin "C") (pinfunction "C_C") (pintype "passive"))
      (node (ref "JP8") (pin "38") (pinfunction "38_38") (pintype "passive"))
    )
    (net (code "68") (name "unconnected-(J3A-P3_VDD-PadP3)") (class "Default")
      (node (ref "J3") (pin "P3") (pinfunction "P3_VDD_P3") (pintype "passive"))
    )
    (net (code "69") (name "unconnected-(J3A-P4_VDD1-PadP4)") (class "Default")
      (node (ref "J3") (pin "P4") (pinfunction "P4_VDD1_P4") (pintype "passive"))
    )
    (net (code "70") (name "unconnected-(J3A-P6_NRST-PadP6)") (class "Default")
      (node (ref "J3") (pin "P6") (pinfunction "P6_NRST_P6") (pintype "passive"))
    )
    (net (code "71") (name "unconnected-(J3A-P7_PC1-PadP7)") (class "Default")
      (node (ref "J3") (pin "P7") (pinfunction "P7_PC1_P7") (pintype "passive"))
    )
    (net (code "72") (name "unconnected-(J3A-P8_PC0-PadP8)") (class "Default")
      (node (ref "J3") (pin "P8") (pinfunction "P8_PC0_P8") (pintype "passive"))
    )
    (net (code "73") (name "unconnected-(J3A-P9_PC3-PadP9)") (class "Default")
      (node (ref "J3") (pin "P9") (pinfunction "P9_PC3_P9") (pintype "passive"))
    )
    (net (code "74") (name "unconnected-(J3A-P10_PC2-PadP10)") (class "Default")
      (node (ref "J3") (pin "P10") (pinfunction "P10_PC2_P10") (pintype "passive"))
    )
    (net (code "75") (name "unconnected-(J3A-P11_PA1-PadP11)") (class "Default")
      (node (ref "J3") (pin "P11") (pinfunction "P11_PA1_P11") (pintype "passive"))
    )
    (net (code "76") (name "unconnected-(J3A-P12_PA0-PadP12)") (class "Default")
      (node (ref "J3") (pin "P12") (pinfunction "P12_PA0_P12") (pintype "passive"))
    )
    (net (code "77") (name "unconnected-(J3A-P13_PA3-PadP13)") (class "Default")
      (node (ref "J3") (pin "P13") (pinfunction "P13_PA3_P13") (pintype "passive"))
    )
    (net (code "78") (name "unconnected-(J3A-P14_PA2-PadP14)") (class "Default")
      (node (ref "J3") (pin "P14") (pinfunction "P14_PA2_P14") (pintype "passive"))
    )
    (net (code "79") (name "unconnected-(J3A-P17_PA7-PadP17)") (class "Default")
      (node (ref "J3") (pin "P17") (pinfunction "P17_PA7_P17") (pintype "passive"))
    )
    (net (code "80") (name "unconnected-(J3A-P18_PA6-PadP18)") (class "Default")
      (node (ref "J3") (pin "P18") (pinfunction "P18_PA6_P18") (pintype "passive"))
    )
    (net (code "81") (name "unconnected-(J3A-P19_PC5-PadP19)") (class "Default")
      (node (ref "J3") (pin "P19") (pinfunction "P19_PC5_P19") (pintype "passive"))
    )
    (net (code "82") (name "unconnected-(J3A-P21_PB1-PadP21)") (class "Default")
      (node (ref "J3") (pin "P21") (pinfunction "P21_PB1_P21") (pintype "passive"))
    )
    (net (code "83") (name "unconnected-(J3A-P24_PB2-PadP24)") (class "Default")
      (node (ref "J3") (pin "P24") (pinfunction "P24_PB2_P24") (pintype "passive"))
    )
    (net (code "84") (name "unconnected-(J3A-P25_PE7-PadP25)") (class "Default")
      (node (ref "J3") (pin "P25") (pinfunction "P25_PE7_P25") (pintype "passive"))
    )
    (net (code "85") (name "unconnected-(J3A-P31_PE13-PadP31)") (class "Default")
      (node (ref "J3") (pin "P31") (pinfunction "P31_PE13_P31") (pintype "passive"))
    )
    (net (code "86") (name "unconnected-(J3A-P33_PE15-PadP33)") (class "Default")
      (node (ref "J3") (pin "P33") (pinfunction "P33_PE15_P33") (pintype "passive"))
    )
    (net (code "87") (name "unconnected-(J3A-P35_PB11-PadP35)") (class "Default")
      (node (ref "J3") (pin "P35") (pinfunction "P35_PB11_P35") (pintype "passive"))
    )
    (net (code "88") (name "unconnected-(J3A-P37_PB13-PadP37)") (class "Default")
      (node (ref "J3") (pin "P37") (pinfunction "P37_PB13_P37") (pintype "passive"))
    )
    (net (code "89") (name "unconnected-(J3A-P38_PB14-PadP38)") (class "Default")
      (node (ref "J3") (pin "P38") (pinfunction "P38_PB14_P38") (pintype "passive"))
    )
    (net (code "90") (name "unconnected-(J3A-P39_PB15-PadP39)") (class "Default")
      (node (ref "J3") (pin "P39") (pinfunction "P39_PB15_P39") (pintype "passive"))
    )
    (net (code "91") (name "unconnected-(J3A-P48_NC-PadP48)") (class "Default")
      (node (ref "J3") (pin "P48") (pinfunction "P48_NC_P48") (pintype "passive"))
    )
    (net (code "92") (name "unconnected-(J3B-P55_3V_1-PadP55)") (class "Default")
      (node (ref "J3") (pin "P55") (pinfunction "P55_3V_1_P55") (pintype "passive"))
    )
    (net (code "93") (name "unconnected-(J3B-P56_3V_2-PadP56)") (class "Default")
      (node (ref "J3") (pin "P56") (pinfunction "P56_3V_2_P56") (pintype "passive"))
    )
    (net (code "94") (name "unconnected-(J3B-P57_PH0-PadP57)") (class "Default")
      (node (ref "J3") (pin "P57") (pinfunction "P57_PH0_P57") (pintype "passive"))
    )
    (net (code "95") (name "unconnected-(J3B-P58_PH1-PadP58)") (class "Default")
      (node (ref "J3") (pin "P58") (pinfunction "P58_PH1_P58") (pintype "passive"))
    )
    (net (code "96") (name "unconnected-(J3B-P59_PC14-PadP59)") (class "Default")
      (node (ref "J3") (pin "P59") (pinfunction "P59_PC14_P59") (pintype "passive"))
    )
    (net (code "97") (name "unconnected-(J3B-P60_PC15-PadP60)") (class "Default")
      (node (ref "J3") (pin "P60") (pinfunction "P60_PC15_P60") (pintype "passive"))
    )
    (net (code "98") (name "unconnected-(J3B-P62_PC13-PadP62)") (class "Default")
      (node (ref "J3") (pin "P62") (pinfunction "P62_PC13_P62") (pintype "passive"))
    )
    (net (code "99") (name "unconnected-(J3B-P63_PE4-PadP63)") (class "Default")
      (node (ref "J3") (pin "P63") (pinfunction "P63_PE4_P63") (pintype "passive"))
    )
    (net (code "100") (name "unconnected-(J3B-P65_PE2-PadP65)") (class "Default")
      (node (ref "J3") (pin "P65") (pinfunction "P65_PE2_P65") (pintype "passive"))
    )
    (net (code "101") (name "unconnected-(J3B-P66_PE3-PadP66)") (class "Default")
      (node (ref "J3") (pin "P66") (pinfunction "P66_PE3_P66") (pintype "passive"))
    )
    (net (code "102") (name "unconnected-(J3B-P67_PE0-PadP67)") (class "Default")
      (node (ref "J3") (pin "P67") (pinfunction "P67_PE0_P67") (pintype "passive"))
    )
    (net (code "103") (name "unconnected-(J3B-P68_PE1-PadP68)") (class "Default")
      (node (ref "J3") (pin "P68") (pinfunction "P68_PE1_P68") (pintype "passive"))
    )
    (net (code "104") (name "unconnected-(J3B-P69_PB8-PadP69)") (class "Default")
      (node (ref "J3") (pin "P69") (pinfunction "P69_PB8_P69") (pintype "passive"))
    )
    (net (code "105") (name "unconnected-(J3B-P70_PB9-PadP70)") (class "Default")
      (node (ref "J3") (pin "P70") (pinfunction "P70_PB9_P70") (pintype "passive"))
    )
    (net (code "106") (name "unconnected-(J3B-P71_BOOT0-PadP71)") (class "Default")
      (node (ref "J3") (pin "P71") (pinfunction "P71_BOOT0_P71") (pintype "passive"))
    )
    (net (code "107") (name "unconnected-(J3B-P72_VDD4-PadP72)") (class "Default")
      (node (ref "J3") (pin "P72") (pinfunction "P72_VDD4_P72") (pintype "passive"))
    )
    (net (code "108") (name "unconnected-(J3B-P73_PB6-PadP73)") (class "Default")
      (node (ref "J3") (pin "P73") (pinfunction "P73_PB6_P73") (pintype "passive"))
    )
    (net (code "109") (name "unconnected-(J3B-P74_PB7-PadP74)") (class "Default")
      (node (ref "J3") (pin "P74") (pinfunction "P74_PB7_P74") (pintype "passive"))
    )
    (net (code "110") (name "unconnected-(J3B-P77_PD7-PadP77)") (class "Default")
      (node (ref "J3") (pin "P77") (pinfunction "P77_PD7_P77") (pintype "passive"))
    )
    (net (code "111") (name "unconnected-(J3B-P81_PD3-PadP81)") (class "Default")
      (node (ref "J3") (pin "P81") (pinfunction "P81_PD3_P81") (pintype "passive"))
    )
    (net (code "112") (name "unconnected-(J3B-P82_PD4-PadP82)") (class "Default")
      (node (ref "J3") (pin "P82") (pinfunction "P82_PD4_P82") (pintype "passive"))
    )
    (net (code "113") (name "unconnected-(J3B-P83_PD1-PadP83)") (class "Default")
      (node (ref "J3") (pin "P83") (pinfunction "P83_PD1_P83") (pintype "passive"))
    )
    (net (code "114") (name "unconnected-(J3B-P86_PD0-PadP86)") (class "Default")
      (node (ref "J3") (pin "P86") (pinfunction "P86_PD0_P86") (pintype "passive"))
    )
    (net (code "115") (name "unconnected-(J3B-P87_PC10-PadP87)") (class "Default")
      (node (ref "J3") (pin "P87") (pinfunction "P87_PC10_P87") (pintype "passive"))
    )
    (net (code "116") (name "unconnected-(J3B-P88_PC11-PadP88)") (class "Default")
      (node (ref "J3") (pin "P88") (pinfunction "P88_PC11_P88") (pintype "passive"))
    )
    (net (code "117") (name "unconnected-(J3B-P89_PA14-PadP89)") (class "Default")
      (node (ref "J3") (pin "P89") (pinfunction "P89_PA14_P89") (pintype "passive"))
    )
    (net (code "118") (name "unconnected-(J3B-P90_PA15-PadP90)") (class "Default")
      (node (ref "J3") (pin "P90") (pinfunction "P90_PA15_P90") (pintype "passive"))
    )
    (net (code "119") (name "unconnected-(J3B-P92_PA13-PadP92)") (class "Default")
      (node (ref "J3") (pin "P92") (pinfunction "P92_PA13_P92") (pintype "passive"))
    )
    (net (code "120") (name "unconnected-(JP5-Pad1)") (class "Default")
      (node (ref "JP5") (pin "1") (pinfunction "1_1") (pintype "passive"))
    )
    (net (code "121") (name "unconnected-(JP5-Pad2)") (class "Default")
      (node (ref "JP5") (pin "2") (pinfunction "2_2") (pintype "passive"))
    )
    (net (code "122") (name "unconnected-(JP5-Pad35)") (class "Default")
      (node (ref "JP5") (pin "35") (pinfunction "35_35") (pintype "passive"))
    )
    (net (code "123") (name "unconnected-(JP5-Pad36)") (class "Default")
      (node (ref "JP5") (pin "36") (pinfunction "36_36") (pintype "passive"))
    )
    (net (code "124") (name "unconnected-(JP5-Pad40)") (class "Default")
      (node (ref "JP5") (pin "40") (pinfunction "40_40") (pintype "passive"))
    )
    (net (code "125") (name "unconnected-(JP6-Pad1)") (class "Default")
      (node (ref "JP6") (pin "1") (pinfunction "1_1") (pintype "passive"))
    )
    (net (code "126") (name "unconnected-(JP6-Pad2)") (class "Default")
      (node (ref "JP6") (pin "2") (pinfunction "2_2") (pintype "passive"))
    )
    (net (code "127") (name "unconnected-(JP6-Pad35)") (class "Default")
      (node (ref "JP6") (pin "35") (pinfunction "35_35") (pintype "passive"))
    )
    (net (code "128") (name "unconnected-(JP6-Pad36)") (class "Default")
      (node (ref "JP6") (pin "36") (pinfunction "36_36") (pintype "passive"))
    )
    (net (code "129") (name "unconnected-(JP6-Pad40)") (class "Default")
      (node (ref "JP6") (pin "40") (pinfunction "40_40") (pintype "passive"))
    )
    (net (code "130") (name "unconnected-(JP7-Pad1)") (class "Default")
      (node (ref "JP7") (pin "1") (pinfunction "1_1") (pintype "passive"))
    )
    (net (code "131") (name "unconnected-(JP7-Pad2)") (class "Default")
      (node (ref "JP7") (pin "2") (pinfunction "2_2") (pintype "passive"))
    )
    (net (code "132") (name "unconnected-(JP7-Pad35)") (class "Default")
      (node (ref "JP7") (pin "35") (pinfunction "35_35") (pintype "passive"))
    )
    (net (code "133") (name "unconnected-(JP7-Pad36)") (class "Default")
      (node (ref "JP7") (pin "36") (pinfunction "36_36") (pintype "passive"))
    )
    (net (code "134") (name "unconnected-(JP7-Pad40)") (class "Default")
      (node (ref "JP7") (pin "40") (pinfunction "40_40") (pintype "passive"))
    )
    (net (code "135") (name "unconnected-(JP8-Pad1)") (class "Default")
      (node (ref "JP8") (pin "1") (pinfunction "1_1") (pintype "passive"))
    )
    (net (code "136") (name "unconnected-(JP8-Pad2)") (class "Default")
      (node (ref "JP8") (pin "2") (pinfunction "2_2") (pintype "passive"))
    )
    (net (code "137") (name "unconnected-(JP8-Pad35)") (class "Default")
      (node (ref "JP8") (pin "35") (pinfunction "35_35") (pintype "passive"))
    )
    (net (code "138") (name "unconnected-(JP8-Pad36)") (class "Default")
      (node (ref "JP8") (pin "36") (pinfunction "36_36") (pintype "passive"))
    )
    (net (code "139") (name "unconnected-(JP8-Pad40)") (class "Default")
      (node (ref "JP8") (pin "40") (pinfunction "40_40") (pintype "passive"))
    )
    (net (code "140") (name "|A_ENC1") (class "Default")
      (node (ref "IC4") (pin "12") (pinfunction "O_12") (pintype "output"))
      (node (ref "J3") (pin "P27") (pinfunction "P27_PE9_P27") (pintype "passive"))
    )
    (net (code "141") (name "|B_ENC1") (class "Default")
      (node (ref "IC4") (pin "10") (pinfunction "O_10") (pintype "output"))
      (node (ref "J3") (pin "P29") (pinfunction "P29_PE11_P29") (pintype "passive"))
    )
  )
)
